# digital.net
KiCad netlist of a schematic drawn in EAGLE
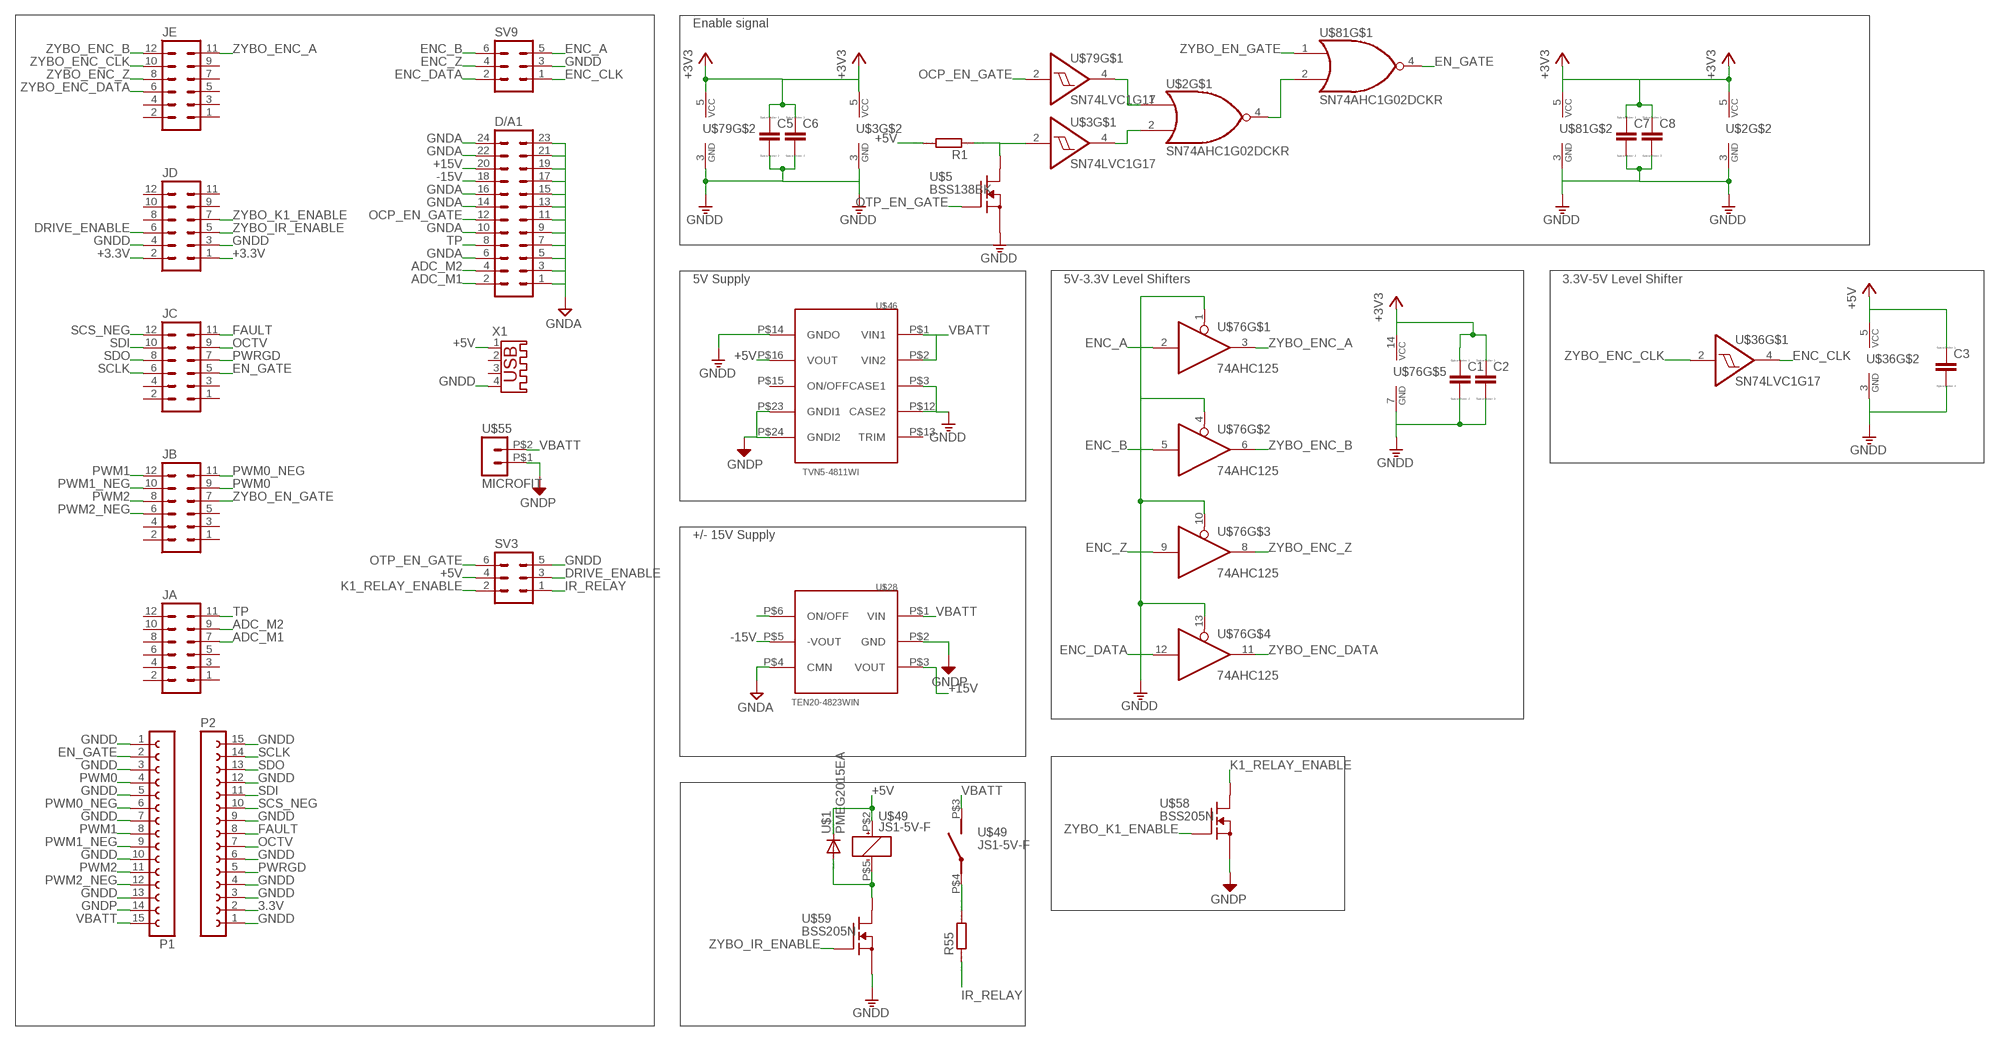
[diagram p0: schematic, sheet 1]

(export (version "E")
  (design (tool "Eeschema 10.0.6"))
  (components
    (comp (ref "C1")
      (value "CC1206")
      (footprint "eagle-import:C1206")
      (libsource (lib "eagle-import") (part "CC1206"))
    )
    (comp (ref "C2")
      (value "CC1206")
      (footprint "eagle-import:C1206")
      (libsource (lib "eagle-import") (part "CC1206"))
    )
    (comp (ref "C3")
      (value "CC1206")
      (footprint "eagle-import:C1206")
      (libsource (lib "eagle-import") (part "CC1206"))
    )
    (comp (ref "C5")
      (value "CC1206")
      (footprint "eagle-import:C1206")
      (libsource (lib "eagle-import") (part "CC1206"))
    )
    (comp (ref "C6")
      (value "CC1206")
      (footprint "eagle-import:C1206")
      (libsource (lib "eagle-import") (part "CC1206"))
    )
    (comp (ref "C7")
      (value "CC1206")
      (footprint "eagle-import:C1206")
      (libsource (lib "eagle-import") (part "CC1206"))
    )
    (comp (ref "C8")
      (value "CC1206")
      (footprint "eagle-import:C1206")
      (libsource (lib "eagle-import") (part "CC1206"))
    )
    (comp (ref "D/A1")
      (value "MA12-2")
      (footprint "eagle-import:MA12-2")
      (libsource (lib "eagle-import") (part "MA12-2"))
    )
    (comp (ref "JA")
      (value "MA06-2")
      (footprint "eagle-import:MA06-2")
      (libsource (lib "eagle-import") (part "MA06-2"))
    )
    (comp (ref "JB")
      (value "MA06-2")
      (footprint "eagle-import:MA06-2")
      (libsource (lib "eagle-import") (part "MA06-2"))
    )
    (comp (ref "JC")
      (value "MA06-2")
      (footprint "eagle-import:MA06-2")
      (libsource (lib "eagle-import") (part "MA06-2"))
    )
    (comp (ref "JD")
      (value "MA06-2")
      (footprint "eagle-import:MA06-2")
      (libsource (lib "eagle-import") (part "MA06-2"))
    )
    (comp (ref "JE")
      (value "MA06-2")
      (footprint "eagle-import:MA06-2")
      (libsource (lib "eagle-import") (part "MA06-2"))
    )
    (comp (ref "P1")
      (value "FE15-1")
      (footprint "eagle-import:FE15")
      (libsource (lib "eagle-import") (part "FE15-1"))
    )
    (comp (ref "P2")
      (value "FE15-1")
      (footprint "eagle-import:FE15")
      (libsource (lib "eagle-import") (part "FE15-1"))
    )
    (comp (ref "R1")
      (value "RR1206")
      (footprint "eagle-import:R1206")
      (libsource (lib "eagle-import") (part "RR1206"))
    )
    (comp (ref "R55")
      (value "RR1206")
      (footprint "eagle-import:R1206")
      (libsource (lib "eagle-import") (part "RR1206"))
    )
    (comp (ref "SV3")
      (value "MA03-2")
      (footprint "eagle-import:MA03-2")
      (libsource (lib "eagle-import") (part "MA03-2"))
    )
    (comp (ref "SV9")
      (value "MA03-2")
      (footprint "eagle-import:MA03-2")
      (libsource (lib "eagle-import") (part "MA03-2"))
    )
    (comp (ref "U$1")
      (value "PMEG2015EA")
      (footprint "eagle-import:SOD323_ST")
      (libsource (lib "eagle-import") (part "PMEG2015EA"))
    )
    (comp (ref "U$2")
      (value "SN74AHC1G02DCKR")
      (footprint "eagle-import:SOT23-5")
      (libsource (lib "eagle-import") (part "SN74AHC1G02DCKR"))
    )
    (comp (ref "U$3")
      (value "SN74LVC1G17")
      (footprint "eagle-import:SOT23-5L")
      (libsource (lib "eagle-import") (part "SN74LVC1G17"))
    )
    (comp (ref "U$5")
      (value "BSS138BK")
      (footprint "eagle-import:SOT23")
      (libsource (lib "eagle-import") (part "BSS138BK"))
    )
    (comp (ref "U$28")
      (value "TEN20-4823WIN")
      (footprint "eagle-import:TEN20-4823")
      (libsource (lib "eagle-import") (part "TEN20-4823WIN"))
    )
    (comp (ref "U$36")
      (value "SN74LVC1G17")
      (footprint "eagle-import:SOT23-5L")
      (libsource (lib "eagle-import") (part "SN74LVC1G17"))
    )
    (comp (ref "U$46")
      (value "TVN5-4811WI")
      (footprint "eagle-import:DIP24")
      (libsource (lib "eagle-import") (part "TVN5-4811WI"))
    )
    (comp (ref "U$49")
      (value "JS1-5V-F")
      (footprint "eagle-import:JS1-5V-F")
      (libsource (lib "eagle-import") (part "JS1-5V-F"))
    )
    (comp (ref "U$55")
      (value "MICROFIT")
      (footprint "eagle-import:MICROFIT-3.0")
      (libsource (lib "eagle-import") (part "MICROFIT"))
    )
    (comp (ref "U$58")
      (value "BSS205N")
      (footprint "eagle-import:SOT23")
      (libsource (lib "eagle-import") (part "BSS205N"))
    )
    (comp (ref "U$59")
      (value "BSS205N")
      (footprint "eagle-import:SOT23")
      (libsource (lib "eagle-import") (part "BSS205N"))
    )
    (comp (ref "U$76")
      (value "74AHC125")
      (footprint "eagle-import:SO14")
      (libsource (lib "eagle-import") (part "74AHC125"))
    )
    (comp (ref "U$79")
      (value "SN74LVC1G17")
      (footprint "eagle-import:SOT23-5L")
      (libsource (lib "eagle-import") (part "SN74LVC1G17"))
    )
    (comp (ref "U$81")
      (value "SN74AHC1G02DCKR")
      (footprint "eagle-import:SOT23-5")
      (libsource (lib "eagle-import") (part "SN74AHC1G02DCKR"))
    )
    (comp (ref "X1")
      (value "USB-A003")
      (footprint "eagle-import:USB-A003")
      (libsource (lib "eagle-import") (part "USB-A003"))
    )
  )
  (nets
    (net (code "1") (name "+3V3") (class "Default")
      (node (ref "C1") (pin "1") (pinfunction "1_1") (pintype "passive"))
      (node (ref "C2") (pin "1") (pinfunction "1_1") (pintype "passive"))
      (node (ref "C5") (pin "1") (pinfunction "1_1") (pintype "passive"))
      (node (ref "C6") (pin "1") (pinfunction "1_1") (pintype "passive"))
      (node (ref "C7") (pin "1") (pinfunction "1_1") (pintype "passive"))
      (node (ref "C8") (pin "1") (pinfunction "1_1") (pintype "passive"))
      (node (ref "U$2") (pin "5") (pinfunction "VCC_5") (pintype "power_in"))
      (node (ref "U$3") (pin "5") (pinfunction "VCC_5") (pintype "power_in"))
      (node (ref "U$76") (pin "14") (pinfunction "VCC_14") (pintype "power_in"))
      (node (ref "U$79") (pin "5") (pinfunction "VCC_5") (pintype "power_in"))
      (node (ref "U$81") (pin "5") (pinfunction "VCC_5") (pintype "power_in"))
    )
    (net (code "2") (name "+5V") (class "Default")
      (node (ref "C3") (pin "1") (pinfunction "1_1") (pintype "passive"))
      (node (ref "R1") (pin "2") (pinfunction "2_2") (pintype "passive"))
      (node (ref "SV3") (pin "4") (pinfunction "4_4") (pintype "passive"))
      (node (ref "U$1") (pin "C") (pinfunction "C_C") (pintype "passive"))
      (node (ref "U$36") (pin "5") (pinfunction "VCC_5") (pintype "power_in"))
      (node (ref "U$46") (pin "P$16") (pinfunction "VOUT_P$16") (pintype "bidirectional"))
      (node (ref "U$49") (pin "P$2") (pinfunction "+_P$2") (pintype "passive"))
      (node (ref "X1") (pin "1") (pinfunction "1_1") (pintype "passive"))
    )
    (net (code "3") (name "/+3.3V") (class "Default")
      (node (ref "JD") (pin "1") (pinfunction "1_1") (pintype "passive"))
      (node (ref "JD") (pin "2") (pinfunction "2_2") (pintype "passive"))
    )
    (net (code "4") (name "/+15V") (class "Default")
      (node (ref "D/A1") (pin "20") (pinfunction "20_20") (pintype "passive"))
      (node (ref "U$28") (pin "P$3") (pinfunction "VOUT_P$3") (pintype "bidirectional"))
    )
    (net (code "5") (name "/-15V") (class "Default")
      (node (ref "D/A1") (pin "18") (pinfunction "18_18") (pintype "passive"))
      (node (ref "U$28") (pin "P$5") (pinfunction "-VOUT_P$5") (pintype "bidirectional"))
    )
    (net (code "6") (name "/3.3V") (class "Default")
      (node (ref "P2") (pin "2") (pinfunction "2_2") (pintype "passive"))
    )
    (net (code "7") (name "/ADC_M1") (class "Default")
      (node (ref "D/A1") (pin "2") (pinfunction "2_2") (pintype "passive"))
      (node (ref "JA") (pin "7") (pinfunction "7_7") (pintype "passive"))
    )
    (net (code "8") (name "/ADC_M2") (class "Default")
      (node (ref "D/A1") (pin "4") (pinfunction "4_4") (pintype "passive"))
      (node (ref "JA") (pin "9") (pinfunction "9_9") (pintype "passive"))
    )
    (net (code "9") (name "/DRIVE_ENABLE") (class "Default")
      (node (ref "JD") (pin "6") (pinfunction "6_6") (pintype "passive"))
      (node (ref "SV3") (pin "3") (pinfunction "3_3") (pintype "passive"))
    )
    (net (code "10") (name "/ENC_A") (class "Default")
      (node (ref "SV9") (pin "5") (pinfunction "5_5") (pintype "passive"))
      (node (ref "U$76") (pin "2") (pinfunction "I_2") (pintype "input"))
    )
    (net (code "11") (name "/ENC_B") (class "Default")
      (node (ref "SV9") (pin "6") (pinfunction "6_6") (pintype "passive"))
      (node (ref "U$76") (pin "5") (pinfunction "I_5") (pintype "input"))
    )
    (net (code "12") (name "/ENC_CLK") (class "Default")
      (node (ref "SV9") (pin "1") (pinfunction "1_1") (pintype "passive"))
      (node (ref "U$36") (pin "4") (pinfunction "O_4") (pintype "output"))
    )
    (net (code "13") (name "/ENC_DATA") (class "Default")
      (node (ref "SV9") (pin "2") (pinfunction "2_2") (pintype "passive"))
      (node (ref "U$76") (pin "12") (pinfunction "I_12") (pintype "input"))
    )
    (net (code "14") (name "/ENC_Z") (class "Default")
      (node (ref "SV9") (pin "4") (pinfunction "4_4") (pintype "passive"))
      (node (ref "U$76") (pin "9") (pinfunction "I_9") (pintype "input"))
    )
    (net (code "15") (name "/EN_GATE") (class "Default")
      (node (ref "JC") (pin "5") (pinfunction "5_5") (pintype "passive"))
      (node (ref "P1") (pin "2") (pinfunction "2_2") (pintype "passive"))
      (node (ref "U$81") (pin "4") (pinfunction "O_4") (pintype "output"))
    )
    (net (code "16") (name "/FAULT") (class "Default")
      (node (ref "JC") (pin "11") (pinfunction "11_11") (pintype "passive"))
      (node (ref "P2") (pin "8") (pinfunction "8_8") (pintype "passive"))
    )
    (net (code "17") (name "/IR_RELAY") (class "Default")
      (node (ref "R55") (pin "1") (pinfunction "1_1") (pintype "passive"))
      (node (ref "SV3") (pin "1") (pinfunction "1_1") (pintype "passive"))
    )
    (net (code "18") (name "/K1_RELAY_ENABLE") (class "Default")
      (node (ref "SV3") (pin "2") (pinfunction "2_2") (pintype "passive"))
      (node (ref "U$58") (pin "3") (pinfunction "D_3") (pintype "passive"))
    )
    (net (code "19") (name "/OCP_EN_GATE") (class "Default")
      (node (ref "D/A1") (pin "12") (pinfunction "12_12") (pintype "passive"))
      (node (ref "U$79") (pin "2") (pinfunction "I_2") (pintype "input"))
    )
    (net (code "20") (name "/OCTV") (class "Default")
      (node (ref "JC") (pin "9") (pinfunction "9_9") (pintype "passive"))
      (node (ref "P2") (pin "7") (pinfunction "7_7") (pintype "passive"))
    )
    (net (code "21") (name "/OTP_EN_GATE") (class "Default")
      (node (ref "SV3") (pin "6") (pinfunction "6_6") (pintype "passive"))
      (node (ref "U$5") (pin "1") (pinfunction "G_1") (pintype "passive"))
    )
    (net (code "22") (name "/PWM0") (class "Default")
      (node (ref "JB") (pin "9") (pinfunction "9_9") (pintype "passive"))
      (node (ref "P1") (pin "4") (pinfunction "4_4") (pintype "passive"))
    )
    (net (code "23") (name "/PWM0_NEG") (class "Default")
      (node (ref "JB") (pin "11") (pinfunction "11_11") (pintype "passive"))
      (node (ref "P1") (pin "6") (pinfunction "6_6") (pintype "passive"))
    )
    (net (code "24") (name "/PWM1") (class "Default")
      (node (ref "JB") (pin "12") (pinfunction "12_12") (pintype "passive"))
      (node (ref "P1") (pin "8") (pinfunction "8_8") (pintype "passive"))
    )
    (net (code "25") (name "/PWM1_NEG") (class "Default")
      (node (ref "JB") (pin "10") (pinfunction "10_10") (pintype "passive"))
      (node (ref "P1") (pin "9") (pinfunction "9_9") (pintype "passive"))
    )
    (net (code "26") (name "/PWM2") (class "Default")
      (node (ref "JB") (pin "8") (pinfunction "8_8") (pintype "passive"))
      (node (ref "P1") (pin "11") (pinfunction "11_11") (pintype "passive"))
    )
    (net (code "27") (name "/PWM2_NEG") (class "Default")
      (node (ref "JB") (pin "6") (pinfunction "6_6") (pintype "passive"))
      (node (ref "P1") (pin "12") (pinfunction "12_12") (pintype "passive"))
    )
    (net (code "28") (name "/PWRGD") (class "Default")
      (node (ref "JC") (pin "7") (pinfunction "7_7") (pintype "passive"))
      (node (ref "P2") (pin "5") (pinfunction "5_5") (pintype "passive"))
    )
    (net (code "29") (name "/SCLK") (class "Default")
      (node (ref "JC") (pin "6") (pinfunction "6_6") (pintype "passive"))
      (node (ref "P2") (pin "14") (pinfunction "14_14") (pintype "passive"))
    )
    (net (code "30") (name "/SCS_NEG") (class "Default")
      (node (ref "JC") (pin "12") (pinfunction "12_12") (pintype "passive"))
      (node (ref "P2") (pin "10") (pinfunction "10_10") (pintype "passive"))
    )
    (net (code "31") (name "/SDI") (class "Default")
      (node (ref "JC") (pin "10") (pinfunction "10_10") (pintype "passive"))
      (node (ref "P2") (pin "11") (pinfunction "11_11") (pintype "passive"))
    )
    (net (code "32") (name "/SDO") (class "Default")
      (node (ref "JC") (pin "8") (pinfunction "8_8") (pintype "passive"))
      (node (ref "P2") (pin "13") (pinfunction "13_13") (pintype "passive"))
    )
    (net (code "33") (name "/TP") (class "Default")
      (node (ref "D/A1") (pin "8") (pinfunction "8_8") (pintype "passive"))
      (node (ref "JA") (pin "11") (pinfunction "11_11") (pintype "passive"))
    )
    (net (code "34") (name "/VBATT") (class "Default")
      (node (ref "P1") (pin "15") (pinfunction "15_15") (pintype "passive"))
      (node (ref "U$28") (pin "P$1") (pinfunction "VIN_P$1") (pintype "bidirectional"))
      (node (ref "U$46") (pin "P$1") (pinfunction "VIN1_P$1") (pintype "bidirectional"))
      (node (ref "U$46") (pin "P$2") (pinfunction "VIN2_P$2") (pintype "bidirectional"))
      (node (ref "U$49") (pin "P$3") (pinfunction "S_P$3") (pintype "passive"))
      (node (ref "U$55") (pin "P$2") (pinfunction "3_P$2") (pintype "passive"))
    )
    (net (code "35") (name "/ZYBO_ENC_A") (class "Default")
      (node (ref "JE") (pin "11") (pinfunction "11_11") (pintype "passive"))
      (node (ref "U$76") (pin "3") (pinfunction "O_3") (pintype "tri_state"))
    )
    (net (code "36") (name "/ZYBO_ENC_B") (class "Default")
      (node (ref "JE") (pin "12") (pinfunction "12_12") (pintype "passive"))
      (node (ref "U$76") (pin "6") (pinfunction "O_6") (pintype "tri_state"))
    )
    (net (code "37") (name "/ZYBO_ENC_CLK") (class "Default")
      (node (ref "JE") (pin "10") (pinfunction "10_10") (pintype "passive"))
      (node (ref "U$36") (pin "2") (pinfunction "I_2") (pintype "input"))
    )
    (net (code "38") (name "/ZYBO_ENC_DATA") (class "Default")
      (node (ref "JE") (pin "6") (pinfunction "6_6") (pintype "passive"))
      (node (ref "U$76") (pin "11") (pinfunction "O_11") (pintype "tri_state"))
    )
    (net (code "39") (name "/ZYBO_ENC_Z") (class "Default")
      (node (ref "JE") (pin "8") (pinfunction "8_8") (pintype "passive"))
      (node (ref "U$76") (pin "8") (pinfunction "O_8") (pintype "tri_state"))
    )
    (net (code "40") (name "/ZYBO_EN_GATE") (class "Default")
      (node (ref "JB") (pin "7") (pinfunction "7_7") (pintype "passive"))
      (node (ref "U$81") (pin "1") (pinfunction "I0_1") (pintype "input"))
    )
    (net (code "41") (name "/ZYBO_IR_ENABLE") (class "Default")
      (node (ref "JD") (pin "5") (pinfunction "5_5") (pintype "passive"))
      (node (ref "U$59") (pin "1") (pinfunction "G_1") (pintype "passive"))
    )
    (net (code "42") (name "/ZYBO_K1_ENABLE") (class "Default")
      (node (ref "JD") (pin "7") (pinfunction "7_7") (pintype "passive"))
      (node (ref "U$58") (pin "1") (pinfunction "G_1") (pintype "passive"))
    )
    (net (code "43") (name "GNDA") (class "Default")
      (node (ref "D/A1") (pin "1") (pinfunction "1_1") (pintype "passive"))
      (node (ref "D/A1") (pin "10") (pinfunction "10_10") (pintype "passive"))
      (node (ref "D/A1") (pin "11") (pinfunction "11_11") (pintype "passive"))
      (node (ref "D/A1") (pin "13") (pinfunction "13_13") (pintype "passive"))
      (node (ref "D/A1") (pin "14") (pinfunction "14_14") (pintype "passive"))
      (node (ref "D/A1") (pin "15") (pinfunction "15_15") (pintype "passive"))
      (node (ref "D/A1") (pin "16") (pinfunction "16_16") (pintype "passive"))
      (node (ref "D/A1") (pin "22") (pinfunction "22_22") (pintype "passive"))
      (node (ref "D/A1") (pin "23") (pinfunction "23_23") (pintype "passive"))
      (node (ref "D/A1") (pin "24") (pinfunction "24_24") (pintype "passive"))
      (node (ref "D/A1") (pin "3") (pinfunction "3_3") (pintype "passive"))
      (node (ref "D/A1") (pin "5") (pinfunction "5_5") (pintype "passive"))
      (node (ref "D/A1") (pin "6") (pinfunction "6_6") (pintype "passive"))
      (node (ref "D/A1") (pin "7") (pinfunction "7_7") (pintype "passive"))
      (node (ref "D/A1") (pin "9") (pinfunction "9_9") (pintype "passive"))
      (node (ref "U$28") (pin "P$4") (pinfunction "CMN_P$4") (pintype "bidirectional"))
    )
    (net (code "44") (name "GNDD") (class "Default")
      (node (ref "C1") (pin "2") (pinfunction "2_2") (pintype "passive"))
      (node (ref "C2") (pin "2") (pinfunction "2_2") (pintype "passive"))
      (node (ref "C3") (pin "2") (pinfunction "2_2") (pintype "passive"))
      (node (ref "C5") (pin "2") (pinfunction "2_2") (pintype "passive"))
      (node (ref "C6") (pin "2") (pinfunction "2_2") (pintype "passive"))
      (node (ref "C7") (pin "2") (pinfunction "2_2") (pintype "passive"))
      (node (ref "C8") (pin "2") (pinfunction "2_2") (pintype "passive"))
      (node (ref "JD") (pin "3") (pinfunction "3_3") (pintype "passive"))
      (node (ref "JD") (pin "4") (pinfunction "4_4") (pintype "passive"))
      (node (ref "P1") (pin "1") (pinfunction "1_1") (pintype "passive"))
      (node (ref "P1") (pin "10") (pinfunction "10_10") (pintype "passive"))
      (node (ref "P1") (pin "13") (pinfunction "13_13") (pintype "passive"))
      (node (ref "P1") (pin "3") (pinfunction "3_3") (pintype "passive"))
      (node (ref "P1") (pin "5") (pinfunction "5_5") (pintype "passive"))
      (node (ref "P1") (pin "7") (pinfunction "7_7") (pintype "passive"))
      (node (ref "P2") (pin "1") (pinfunction "1_1") (pintype "passive"))
      (node (ref "P2") (pin "12") (pinfunction "12_12") (pintype "passive"))
      (node (ref "P2") (pin "15") (pinfunction "15_15") (pintype "passive"))
      (node (ref "P2") (pin "3") (pinfunction "3_3") (pintype "passive"))
      (node (ref "P2") (pin "4") (pinfunction "4_4") (pintype "passive"))
      (node (ref "P2") (pin "6") (pinfunction "6_6") (pintype "passive"))
      (node (ref "P2") (pin "9") (pinfunction "9_9") (pintype "passive"))
      (node (ref "SV3") (pin "5") (pinfunction "5_5") (pintype "passive"))
      (node (ref "SV9") (pin "3") (pinfunction "3_3") (pintype "passive"))
      (node (ref "U$2") (pin "3") (pinfunction "GND_3") (pintype "power_in"))
      (node (ref "U$3") (pin "3") (pinfunction "GND_3") (pintype "power_in"))
      (node (ref "U$36") (pin "3") (pinfunction "GND_3") (pintype "power_in"))
      (node (ref "U$46") (pin "P$12") (pinfunction "CASE2_P$12") (pintype "bidirectional"))
      (node (ref "U$46") (pin "P$14") (pinfunction "GNDO_P$14") (pintype "bidirectional"))
      (node (ref "U$46") (pin "P$3") (pinfunction "CASE1_P$3") (pintype "bidirectional"))
      (node (ref "U$5") (pin "2") (pinfunction "S_2") (pintype "passive"))
      (node (ref "U$59") (pin "2") (pinfunction "S_2") (pintype "passive"))
      (node (ref "U$76") (pin "1") (pinfunction "OE_1") (pintype "input"))
      (node (ref "U$76") (pin "10") (pinfunction "OE_10") (pintype "input"))
      (node (ref "U$76") (pin "13") (pinfunction "OE_13") (pintype "input"))
      (node (ref "U$76") (pin "4") (pinfunction "OE_4") (pintype "input"))
      (node (ref "U$76") (pin "7") (pinfunction "GND_7") (pintype "power_in"))
      (node (ref "U$79") (pin "3") (pinfunction "GND_3") (pintype "power_in"))
      (node (ref "U$81") (pin "3") (pinfunction "GND_3") (pintype "power_in"))
      (node (ref "X1") (pin "4") (pinfunction "4_4") (pintype "passive"))
    )
    (net (code "45") (name "GNDP") (class "Default")
      (node (ref "P1") (pin "14") (pinfunction "14_14") (pintype "passive"))
      (node (ref "U$28") (pin "P$2") (pinfunction "GND_P$2") (pintype "bidirectional"))
      (node (ref "U$46") (pin "P$23") (pinfunction "GNDI1_P$23") (pintype "bidirectional"))
      (node (ref "U$46") (pin "P$24") (pinfunction "GNDI2_P$24") (pintype "bidirectional"))
      (node (ref "U$55") (pin "P$1") (pinfunction "2_P$1") (pintype "passive"))
      (node (ref "U$58") (pin "2") (pinfunction "S_2") (pintype "passive"))
    )
    (net (code "46") (name "Net-(U$2A-I0)") (class "Default")
      (node (ref "U$2") (pin "1") (pinfunction "I0_1") (pintype "input"))
      (node (ref "U$79") (pin "4") (pinfunction "O_4") (pintype "output"))
    )
    (net (code "47") (name "Net-(U$2A-I1)") (class "Default")
      (node (ref "U$2") (pin "2") (pinfunction "I1_2") (pintype "input"))
      (node (ref "U$3") (pin "4") (pinfunction "O_4") (pintype "output"))
    )
    (net (code "48") (name "Net-(U$2A-O)") (class "Default")
      (node (ref "U$2") (pin "4") (pinfunction "O_4") (pintype "output"))
      (node (ref "U$81") (pin "2") (pinfunction "I1_2") (pintype "input"))
    )
    (net (code "49") (name "Net-(U$3A-I)") (class "Default")
      (node (ref "R1") (pin "1") (pinfunction "1_1") (pintype "passive"))
      (node (ref "U$3") (pin "2") (pinfunction "I_2") (pintype "input"))
      (node (ref "U$5") (pin "3") (pinfunction "D_3") (pintype "passive"))
    )
    (net (code "50") (name "Net-(U$49A--)") (class "Default")
      (node (ref "U$1") (pin "A") (pinfunction "A_A") (pintype "passive"))
      (node (ref "U$49") (pin "P$5") (pinfunction "-_P$5") (pintype "passive"))
      (node (ref "U$59") (pin "3") (pinfunction "D_3") (pintype "passive"))
    )
    (net (code "51") (name "Net-(U$49B-P)") (class "Default")
      (node (ref "R55") (pin "2") (pinfunction "2_2") (pintype "passive"))
      (node (ref "U$49") (pin "P$4") (pinfunction "P_P$4") (pintype "passive"))
    )
    (net (code "52") (name "unconnected-(D/A1-Pad17)") (class "Default")
      (node (ref "D/A1") (pin "17") (pinfunction "17_17") (pintype "passive"))
    )
    (net (code "53") (name "unconnected-(D/A1-Pad19)") (class "Default")
      (node (ref "D/A1") (pin "19") (pinfunction "19_19") (pintype "passive"))
    )
    (net (code "54") (name "unconnected-(D/A1-Pad21)") (class "Default")
      (node (ref "D/A1") (pin "21") (pinfunction "21_21") (pintype "passive"))
    )
    (net (code "55") (name "unconnected-(JA-Pad1)") (class "Default")
      (node (ref "JA") (pin "1") (pinfunction "1_1") (pintype "passive"))
    )
    (net (code "56") (name "unconnected-(JA-Pad2)") (class "Default")
      (node (ref "JA") (pin "2") (pinfunction "2_2") (pintype "passive"))
    )
    (net (code "57") (name "unconnected-(JA-Pad3)") (class "Default")
      (node (ref "JA") (pin "3") (pinfunction "3_3") (pintype "passive"))
    )
    (net (code "58") (name "unconnected-(JA-Pad4)") (class "Default")
      (node (ref "JA") (pin "4") (pinfunction "4_4") (pintype "passive"))
    )
    (net (code "59") (name "unconnected-(JA-Pad5)") (class "Default")
      (node (ref "JA") (pin "5") (pinfunction "5_5") (pintype "passive"))
    )
    (net (code "60") (name "unconnected-(JA-Pad6)") (class "Default")
      (node (ref "JA") (pin "6") (pinfunction "6_6") (pintype "passive"))
    )
    (net (code "61") (name "unconnected-(JA-Pad8)") (class "Default")
      (node (ref "JA") (pin "8") (pinfunction "8_8") (pintype "passive"))
    )
    (net (code "62") (name "unconnected-(JA-Pad10)") (class "Default")
      (node (ref "JA") (pin "10") (pinfunction "10_10") (pintype "passive"))
    )
    (net (code "63") (name "unconnected-(JA-Pad12)") (class "Default")
      (node (ref "JA") (pin "12") (pinfunction "12_12") (pintype "passive"))
    )
    (net (code "64") (name "unconnected-(JB-Pad1)") (class "Default")
      (node (ref "JB") (pin "1") (pinfunction "1_1") (pintype "passive"))
    )
    (net (code "65") (name "unconnected-(JB-Pad2)") (class "Default")
      (node (ref "JB") (pin "2") (pinfunction "2_2") (pintype "passive"))
    )
    (net (code "66") (name "unconnected-(JB-Pad3)") (class "Default")
      (node (ref "JB") (pin "3") (pinfunction "3_3") (pintype "passive"))
    )
    (net (code "67") (name "unconnected-(JB-Pad4)") (class "Default")
      (node (ref "JB") (pin "4") (pinfunction "4_4") (pintype "passive"))
    )
    (net (code "68") (name "unconnected-(JB-Pad5)") (class "Default")
      (node (ref "JB") (pin "5") (pinfunction "5_5") (pintype "passive"))
    )
    (net (code "69") (name "unconnected-(JC-Pad1)") (class "Default")
      (node (ref "JC") (pin "1") (pinfunction "1_1") (pintype "passive"))
    )
    (net (code "70") (name "unconnected-(JC-Pad2)") (class "Default")
      (node (ref "JC") (pin "2") (pinfunction "2_2") (pintype "passive"))
    )
    (net (code "71") (name "unconnected-(JC-Pad3)") (class "Default")
      (node (ref "JC") (pin "3") (pinfunction "3_3") (pintype "passive"))
    )
    (net (code "72") (name "unconnected-(JC-Pad4)") (class "Default")
      (node (ref "JC") (pin "4") (pinfunction "4_4") (pintype "passive"))
    )
    (net (code "73") (name "unconnected-(JD-Pad8)") (class "Default")
      (node (ref "JD") (pin "8") (pinfunction "8_8") (pintype "passive"))
    )
    (net (code "74") (name "unconnected-(JD-Pad9)") (class "Default")
      (node (ref "JD") (pin "9") (pinfunction "9_9") (pintype "passive"))
    )
    (net (code "75") (name "unconnected-(JD-Pad10)") (class "Default")
      (node (ref "JD") (pin "10") (pinfunction "10_10") (pintype "passive"))
    )
    (net (code "76") (name "unconnected-(JD-Pad11)") (class "Default")
      (node (ref "JD") (pin "11") (pinfunction "11_11") (pintype "passive"))
    )
    (net (code "77") (name "unconnected-(JD-Pad12)") (class "Default")
      (node (ref "JD") (pin "12") (pinfunction "12_12") (pintype "passive"))
    )
    (net (code "78") (name "unconnected-(JE-Pad1)") (class "Default")
      (node (ref "JE") (pin "1") (pinfunction "1_1") (pintype "passive"))
    )
    (net (code "79") (name "unconnected-(JE-Pad2)") (class "Default")
      (node (ref "JE") (pin "2") (pinfunction "2_2") (pintype "passive"))
    )
    (net (code "80") (name "unconnected-(JE-Pad3)") (class "Default")
      (node (ref "JE") (pin "3") (pinfunction "3_3") (pintype "passive"))
    )
    (net (code "81") (name "unconnected-(JE-Pad4)") (class "Default")
      (node (ref "JE") (pin "4") (pinfunction "4_4") (pintype "passive"))
    )
    (net (code "82") (name "unconnected-(JE-Pad5)") (class "Default")
      (node (ref "JE") (pin "5") (pinfunction "5_5") (pintype "passive"))
    )
    (net (code "83") (name "unconnected-(JE-Pad7)") (class "Default")
      (node (ref "JE") (pin "7") (pinfunction "7_7") (pintype "passive"))
    )
    (net (code "84") (name "unconnected-(JE-Pad9)") (class "Default")
      (node (ref "JE") (pin "9") (pinfunction "9_9") (pintype "passive"))
    )
    (net (code "85") (name "unconnected-(U$28-ON{slash}OFF-PadP$6)") (class "Default")
      (node (ref "U$28") (pin "P$6") (pinfunction "ON/OFF_P$6") (pintype "bidirectional"))
    )
    (net (code "86") (name "unconnected-(U$46-ON{slash}OFF-PadP$15)") (class "Default")
      (node (ref "U$46") (pin "P$15") (pinfunction "ON/OFF_P$15") (pintype "bidirectional"))
    )
    (net (code "87") (name "unconnected-(U$46-TRIM-PadP$13)") (class "Default")
      (node (ref "U$46") (pin "P$13") (pinfunction "TRIM_P$13") (pintype "bidirectional"))
    )
    (net (code "88") (name "unconnected-(X1-Pad2)") (class "Default")
      (node (ref "X1") (pin "2") (pinfunction "2_2") (pintype "passive"))
    )
    (net (code "89") (name "unconnected-(X1-Pad3)") (class "Default")
      (node (ref "X1") (pin "3") (pinfunction "3_3") (pintype "passive"))
    )
  )
)
